# ESP32_LED_Matrix.net
KiCad netlist of a schematic drawn in Altium Designer
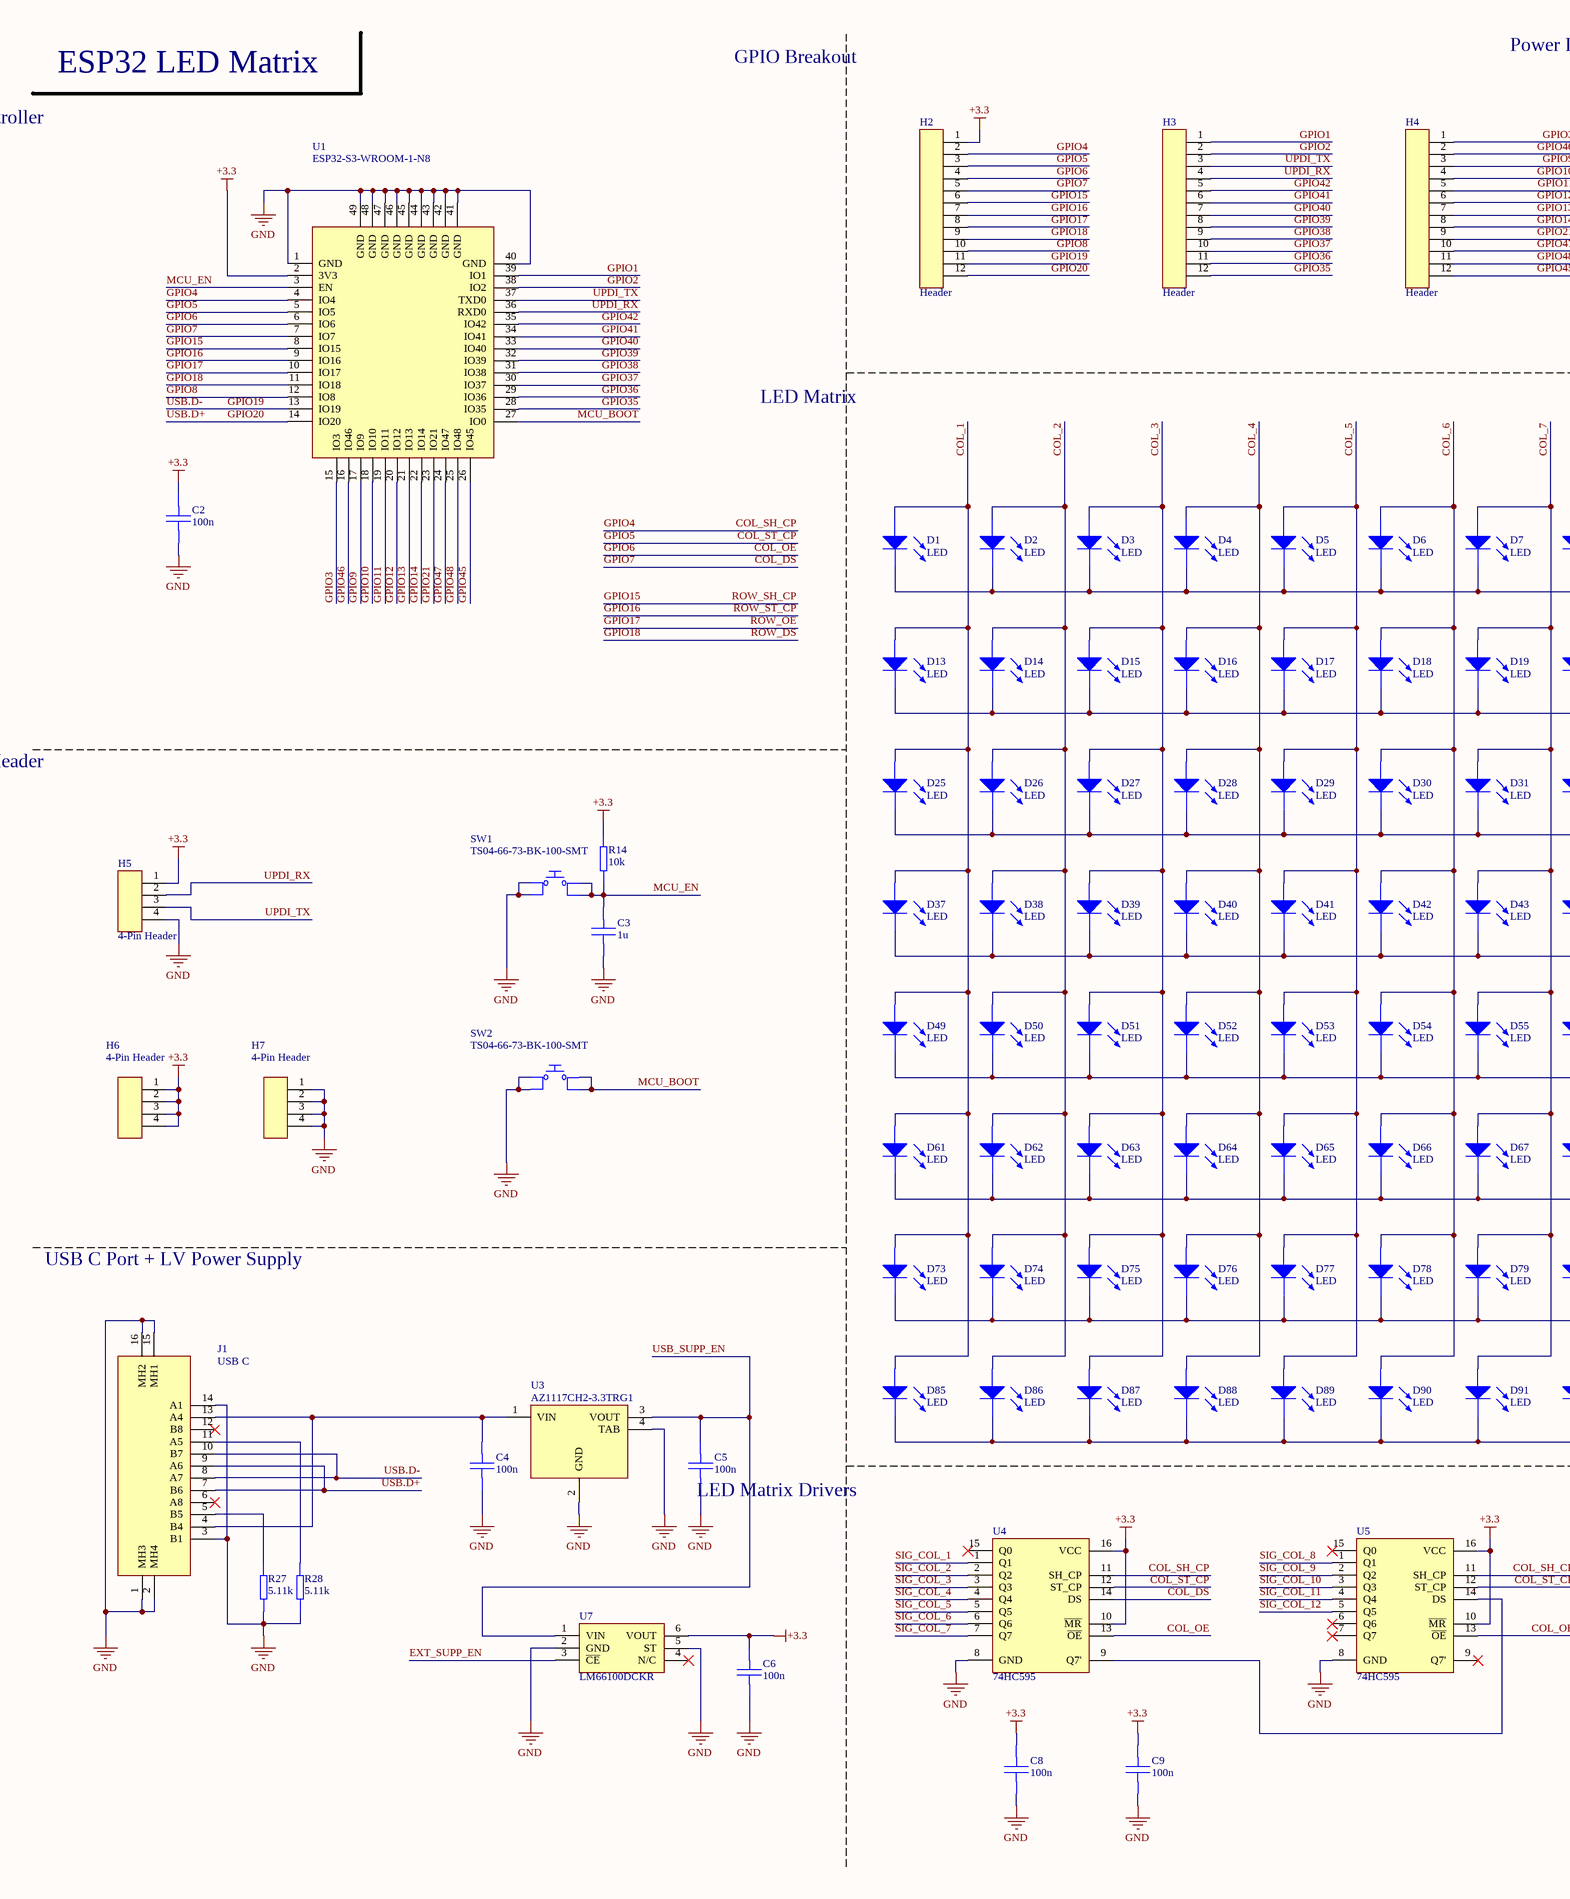
[diagram p0: ESP32_LED_Matrix.SchDoc, left]
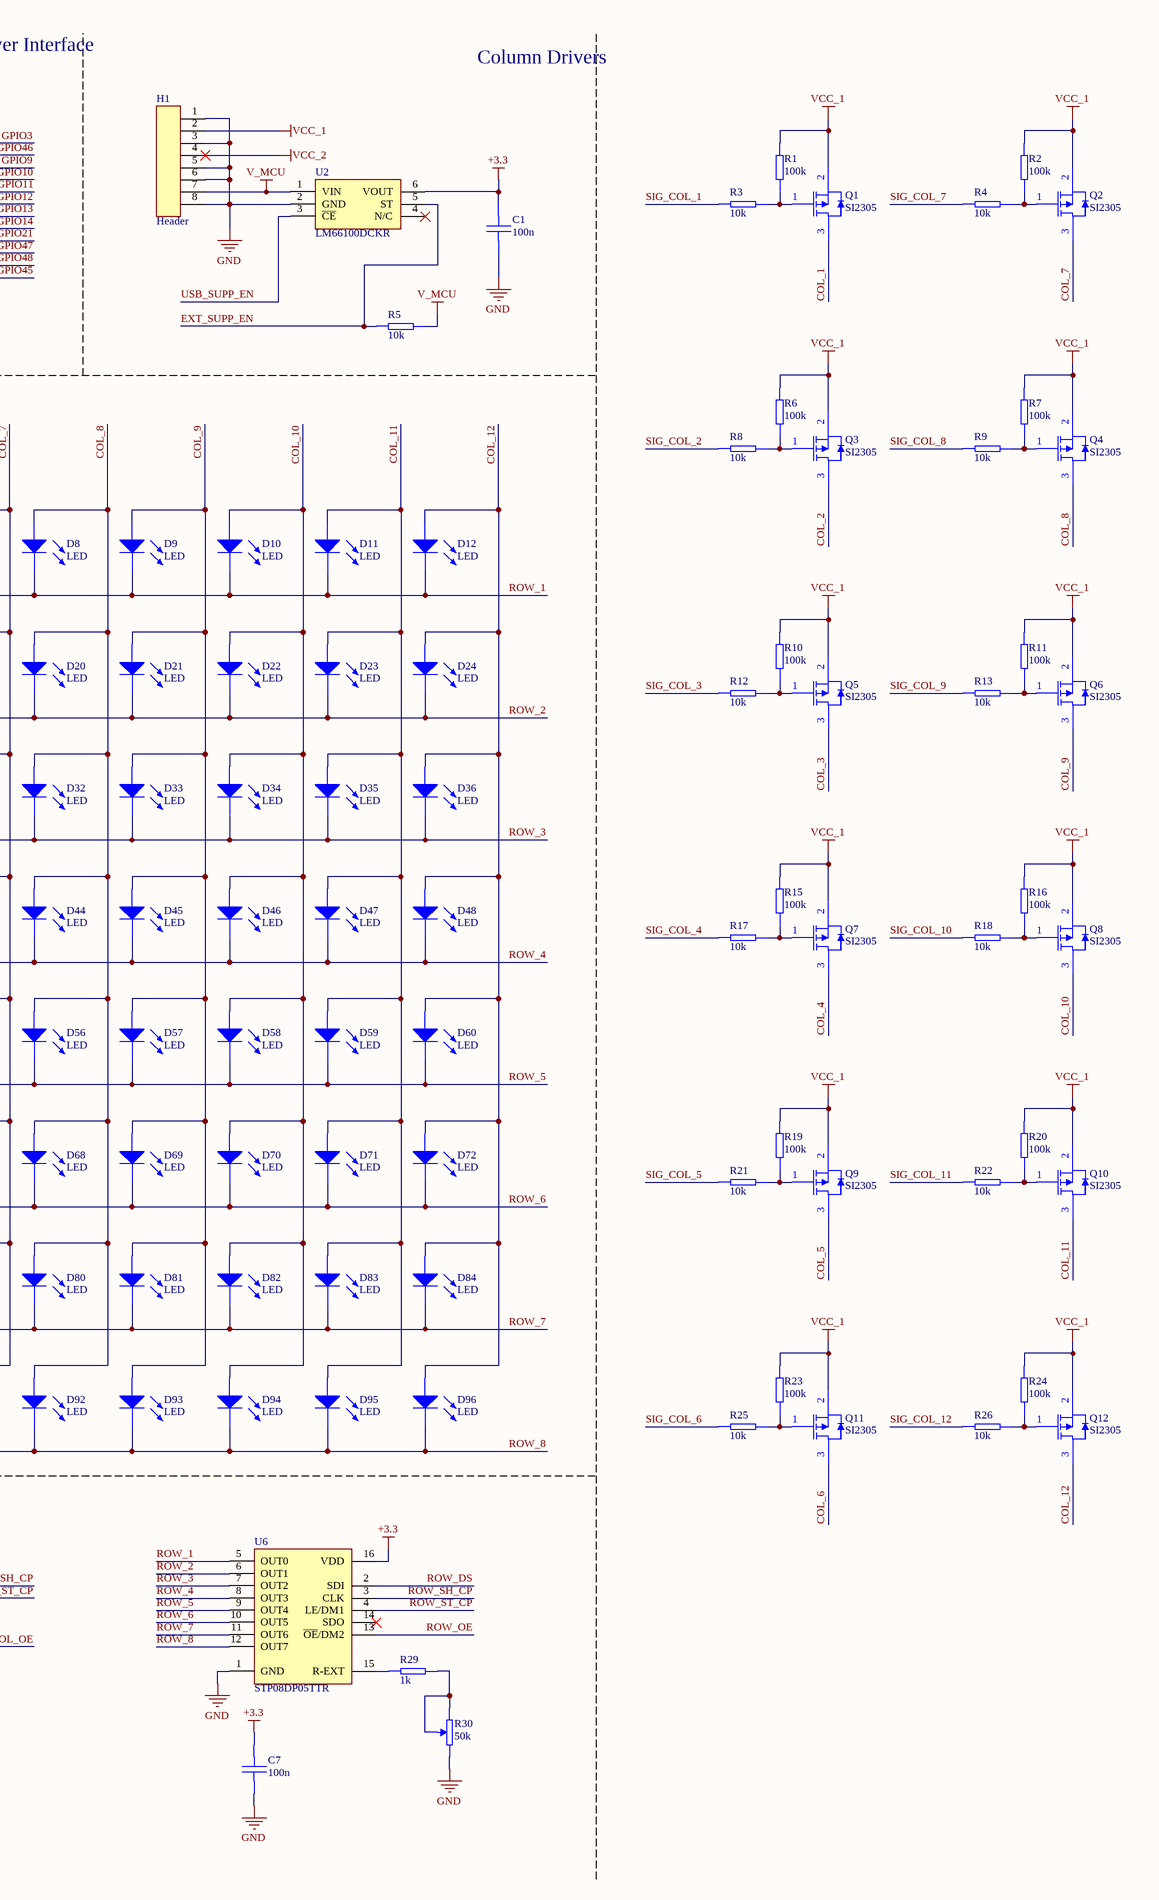
[diagram p1: ESP32_LED_Matrix.SchDoc, right]

(export (version "E")
  (design (tool "Eeschema 10.0.6"))
  (components
    (comp (ref "C1")
      (value "100n")
      (footprint "CAP0805")
      (description "Non Polarized Capacitor")
      (libsource (lib "HT2.2") (part "Capacitor - Non Polarized"))
    )
    (comp (ref "C2")
      (value "100n")
      (footprint "CAP0805")
      (description "Non Polarized Capacitor")
      (libsource (lib "HT2.2") (part "Capacitor - Non Polarized"))
    )
    (comp (ref "C3")
      (value "1u")
      (footprint "CAP0805")
      (description "Non Polarized Capacitor")
      (libsource (lib "HT2.2") (part "Capacitor - Non Polarized"))
    )
    (comp (ref "C4")
      (value "100n")
      (footprint "CAP0805")
      (description "Non Polarized Capacitor")
      (libsource (lib "TD") (part "Capacitor - Non Polarized"))
    )
    (comp (ref "C5")
      (value "100n")
      (footprint "CAP0805")
      (description "Non Polarized Capacitor")
      (libsource (lib "HT2.2") (part "Capacitor - Non Polarized"))
    )
    (comp (ref "C6")
      (value "100n")
      (footprint "CAP0805")
      (description "Non Polarized Capacitor")
      (libsource (lib "HT2.2") (part "Capacitor - Non Polarized"))
    )
    (comp (ref "C7")
      (value "100n")
      (footprint "CAP0805")
      (description "Non Polarized Capacitor")
      (libsource (lib "TD") (part "Capacitor - Non Polarized"))
    )
    (comp (ref "C8")
      (value "100n")
      (footprint "CAP0805")
      (description "Non Polarized Capacitor")
      (libsource (lib "TD") (part "Capacitor - Non Polarized"))
    )
    (comp (ref "C9")
      (value "100n")
      (footprint "CAP0805")
      (description "Non Polarized Capacitor")
      (libsource (lib "TD") (part "Capacitor - Non Polarized"))
    )
    (comp (ref "D1")
      (value "LED")
      (footprint "LEDM2012X80N")
      (description "General Purpose LED")
      (libsource (lib "TD") (part "LED"))
    )
    (comp (ref "D2")
      (value "LED")
      (footprint "LEDM2012X80N")
      (description "General Purpose LED")
      (libsource (lib "TD") (part "LED"))
    )
    (comp (ref "D3")
      (value "LED")
      (footprint "LEDM2012X80N")
      (description "General Purpose LED")
      (libsource (lib "TD") (part "LED"))
    )
    (comp (ref "D4")
      (value "LED")
      (footprint "LEDM2012X80N")
      (description "General Purpose LED")
      (libsource (lib "TD") (part "LED"))
    )
    (comp (ref "D5")
      (value "LED")
      (footprint "LEDM2012X80N")
      (description "General Purpose LED")
      (libsource (lib "TD") (part "LED"))
    )
    (comp (ref "D6")
      (value "LED")
      (footprint "LEDM2012X80N")
      (description "General Purpose LED")
      (libsource (lib "TD") (part "LED"))
    )
    (comp (ref "D7")
      (value "LED")
      (footprint "LEDM2012X80N")
      (description "General Purpose LED")
      (libsource (lib "TD") (part "LED"))
    )
    (comp (ref "D8")
      (value "LED")
      (footprint "LEDM2012X80N")
      (description "General Purpose LED")
      (libsource (lib "TD") (part "LED"))
    )
    (comp (ref "D9")
      (value "LED")
      (footprint "LEDM2012X80N")
      (description "General Purpose LED")
      (libsource (lib "TD") (part "LED"))
    )
    (comp (ref "D10")
      (value "LED")
      (footprint "LEDM2012X80N")
      (description "General Purpose LED")
      (libsource (lib "TD") (part "LED"))
    )
    (comp (ref "D11")
      (value "LED")
      (footprint "LEDM2012X80N")
      (description "General Purpose LED")
      (libsource (lib "TD") (part "LED"))
    )
    (comp (ref "D12")
      (value "LED")
      (footprint "LEDM2012X80N")
      (description "General Purpose LED")
      (libsource (lib "TD") (part "LED"))
    )
    (comp (ref "D13")
      (value "LED")
      (footprint "LEDM2012X80N")
      (description "General Purpose LED")
      (libsource (lib "TD") (part "LED"))
    )
    (comp (ref "D14")
      (value "LED")
      (footprint "LEDM2012X80N")
      (description "General Purpose LED")
      (libsource (lib "TD") (part "LED"))
    )
    (comp (ref "D15")
      (value "LED")
      (footprint "LEDM2012X80N")
      (description "General Purpose LED")
      (libsource (lib "TD") (part "LED"))
    )
    (comp (ref "D16")
      (value "LED")
      (footprint "LEDM2012X80N")
      (description "General Purpose LED")
      (libsource (lib "TD") (part "LED"))
    )
    (comp (ref "D17")
      (value "LED")
      (footprint "LEDM2012X80N")
      (description "General Purpose LED")
      (libsource (lib "TD") (part "LED"))
    )
    (comp (ref "D18")
      (value "LED")
      (footprint "LEDM2012X80N")
      (description "General Purpose LED")
      (libsource (lib "TD") (part "LED"))
    )
    (comp (ref "D19")
      (value "LED")
      (footprint "LEDM2012X80N")
      (description "General Purpose LED")
      (libsource (lib "TD") (part "LED"))
    )
    (comp (ref "D20")
      (value "LED")
      (footprint "LEDM2012X80N")
      (description "General Purpose LED")
      (libsource (lib "TD") (part "LED"))
    )
    (comp (ref "D21")
      (value "LED")
      (footprint "LEDM2012X80N")
      (description "General Purpose LED")
      (libsource (lib "TD") (part "LED"))
    )
    (comp (ref "D22")
      (value "LED")
      (footprint "LEDM2012X80N")
      (description "General Purpose LED")
      (libsource (lib "TD") (part "LED"))
    )
    (comp (ref "D23")
      (value "LED")
      (footprint "LEDM2012X80N")
      (description "General Purpose LED")
      (libsource (lib "TD") (part "LED"))
    )
    (comp (ref "D24")
      (value "LED")
      (footprint "LEDM2012X80N")
      (description "General Purpose LED")
      (libsource (lib "TD") (part "LED"))
    )
    (comp (ref "D25")
      (value "LED")
      (footprint "LEDM2012X80N")
      (description "General Purpose LED")
      (libsource (lib "TD") (part "LED"))
    )
    (comp (ref "D26")
      (value "LED")
      (footprint "LEDM2012X80N")
      (description "General Purpose LED")
      (libsource (lib "TD") (part "LED"))
    )
    (comp (ref "D27")
      (value "LED")
      (footprint "LEDM2012X80N")
      (description "General Purpose LED")
      (libsource (lib "TD") (part "LED"))
    )
    (comp (ref "D28")
      (value "LED")
      (footprint "LEDM2012X80N")
      (description "General Purpose LED")
      (libsource (lib "TD") (part "LED"))
    )
    (comp (ref "D29")
      (value "LED")
      (footprint "LEDM2012X80N")
      (description "General Purpose LED")
      (libsource (lib "TD") (part "LED"))
    )
    (comp (ref "D30")
      (value "LED")
      (footprint "LEDM2012X80N")
      (description "General Purpose LED")
      (libsource (lib "TD") (part "LED"))
    )
    (comp (ref "D31")
      (value "LED")
      (footprint "LEDM2012X80N")
      (description "General Purpose LED")
      (libsource (lib "TD") (part "LED"))
    )
    (comp (ref "D32")
      (value "LED")
      (footprint "LEDM2012X80N")
      (description "General Purpose LED")
      (libsource (lib "TD") (part "LED"))
    )
    (comp (ref "D33")
      (value "LED")
      (footprint "LEDM2012X80N")
      (description "General Purpose LED")
      (libsource (lib "TD") (part "LED"))
    )
    (comp (ref "D34")
      (value "LED")
      (footprint "LEDM2012X80N")
      (description "General Purpose LED")
      (libsource (lib "TD") (part "LED"))
    )
    (comp (ref "D35")
      (value "LED")
      (footprint "LEDM2012X80N")
      (description "General Purpose LED")
      (libsource (lib "TD") (part "LED"))
    )
    (comp (ref "D36")
      (value "LED")
      (footprint "LEDM2012X80N")
      (description "General Purpose LED")
      (libsource (lib "TD") (part "LED"))
    )
    (comp (ref "D37")
      (value "LED")
      (footprint "LEDM2012X80N")
      (description "General Purpose LED")
      (libsource (lib "TD") (part "LED"))
    )
    (comp (ref "D38")
      (value "LED")
      (footprint "LEDM2012X80N")
      (description "General Purpose LED")
      (libsource (lib "TD") (part "LED"))
    )
    (comp (ref "D39")
      (value "LED")
      (footprint "LEDM2012X80N")
      (description "General Purpose LED")
      (libsource (lib "TD") (part "LED"))
    )
    (comp (ref "D40")
      (value "LED")
      (footprint "LEDM2012X80N")
      (description "General Purpose LED")
      (libsource (lib "TD") (part "LED"))
    )
    (comp (ref "D41")
      (value "LED")
      (footprint "LEDM2012X80N")
      (description "General Purpose LED")
      (libsource (lib "TD") (part "LED"))
    )
    (comp (ref "D42")
      (value "LED")
      (footprint "LEDM2012X80N")
      (description "General Purpose LED")
      (libsource (lib "TD") (part "LED"))
    )
    (comp (ref "D43")
      (value "LED")
      (footprint "LEDM2012X80N")
      (description "General Purpose LED")
      (libsource (lib "TD") (part "LED"))
    )
    (comp (ref "D44")
      (value "LED")
      (footprint "LEDM2012X80N")
      (description "General Purpose LED")
      (libsource (lib "TD") (part "LED"))
    )
    (comp (ref "D45")
      (value "LED")
      (footprint "LEDM2012X80N")
      (description "General Purpose LED")
      (libsource (lib "TD") (part "LED"))
    )
    (comp (ref "D46")
      (value "LED")
      (footprint "LEDM2012X80N")
      (description "General Purpose LED")
      (libsource (lib "TD") (part "LED"))
    )
    (comp (ref "D47")
      (value "LED")
      (footprint "LEDM2012X80N")
      (description "General Purpose LED")
      (libsource (lib "TD") (part "LED"))
    )
    (comp (ref "D48")
      (value "LED")
      (footprint "LEDM2012X80N")
      (description "General Purpose LED")
      (libsource (lib "TD") (part "LED"))
    )
    (comp (ref "D49")
      (value "LED")
      (footprint "LEDM2012X80N")
      (description "General Purpose LED")
      (libsource (lib "TD") (part "LED"))
    )
    (comp (ref "D50")
      (value "LED")
      (footprint "LEDM2012X80N")
      (description "General Purpose LED")
      (libsource (lib "TD") (part "LED"))
    )
    (comp (ref "D51")
      (value "LED")
      (footprint "LEDM2012X80N")
      (description "General Purpose LED")
      (libsource (lib "TD") (part "LED"))
    )
    (comp (ref "D52")
      (value "LED")
      (footprint "LEDM2012X80N")
      (description "General Purpose LED")
      (libsource (lib "TD") (part "LED"))
    )
    (comp (ref "D53")
      (value "LED")
      (footprint "LEDM2012X80N")
      (description "General Purpose LED")
      (libsource (lib "TD") (part "LED"))
    )
    (comp (ref "D54")
      (value "LED")
      (footprint "LEDM2012X80N")
      (description "General Purpose LED")
      (libsource (lib "TD") (part "LED"))
    )
    (comp (ref "D55")
      (value "LED")
      (footprint "LEDM2012X80N")
      (description "General Purpose LED")
      (libsource (lib "TD") (part "LED"))
    )
    (comp (ref "D56")
      (value "LED")
      (footprint "LEDM2012X80N")
      (description "General Purpose LED")
      (libsource (lib "TD") (part "LED"))
    )
    (comp (ref "D57")
      (value "LED")
      (footprint "LEDM2012X80N")
      (description "General Purpose LED")
      (libsource (lib "TD") (part "LED"))
    )
    (comp (ref "D58")
      (value "LED")
      (footprint "LEDM2012X80N")
      (description "General Purpose LED")
      (libsource (lib "TD") (part "LED"))
    )
    (comp (ref "D59")
      (value "LED")
      (footprint "LEDM2012X80N")
      (description "General Purpose LED")
      (libsource (lib "TD") (part "LED"))
    )
    (comp (ref "D60")
      (value "LED")
      (footprint "LEDM2012X80N")
      (description "General Purpose LED")
      (libsource (lib "TD") (part "LED"))
    )
    (comp (ref "D61")
      (value "LED")
      (footprint "LEDM2012X80N")
      (description "General Purpose LED")
      (libsource (lib "TD") (part "LED"))
    )
    (comp (ref "D62")
      (value "LED")
      (footprint "LEDM2012X80N")
      (description "General Purpose LED")
      (libsource (lib "TD") (part "LED"))
    )
    (comp (ref "D63")
      (value "LED")
      (footprint "LEDM2012X80N")
      (description "General Purpose LED")
      (libsource (lib "TD") (part "LED"))
    )
    (comp (ref "D64")
      (value "LED")
      (footprint "LEDM2012X80N")
      (description "General Purpose LED")
      (libsource (lib "TD") (part "LED"))
    )
    (comp (ref "D65")
      (value "LED")
      (footprint "LEDM2012X80N")
      (description "General Purpose LED")
      (libsource (lib "TD") (part "LED"))
    )
    (comp (ref "D66")
      (value "LED")
      (footprint "LEDM2012X80N")
      (description "General Purpose LED")
      (libsource (lib "TD") (part "LED"))
    )
    (comp (ref "D67")
      (value "LED")
      (footprint "LEDM2012X80N")
      (description "General Purpose LED")
      (libsource (lib "TD") (part "LED"))
    )
    (comp (ref "D68")
      (value "LED")
      (footprint "LEDM2012X80N")
      (description "General Purpose LED")
      (libsource (lib "TD") (part "LED"))
    )
    (comp (ref "D69")
      (value "LED")
      (footprint "LEDM2012X80N")
      (description "General Purpose LED")
      (libsource (lib "TD") (part "LED"))
    )
    (comp (ref "D70")
      (value "LED")
      (footprint "LEDM2012X80N")
      (description "General Purpose LED")
      (libsource (lib "TD") (part "LED"))
    )
    (comp (ref "D71")
      (value "LED")
      (footprint "LEDM2012X80N")
      (description "General Purpose LED")
      (libsource (lib "TD") (part "LED"))
    )
    (comp (ref "D72")
      (value "LED")
      (footprint "LEDM2012X80N")
      (description "General Purpose LED")
      (libsource (lib "TD") (part "LED"))
    )
    (comp (ref "D73")
      (value "LED")
      (footprint "LEDM2012X80N")
      (description "General Purpose LED")
      (libsource (lib "TD") (part "LED"))
    )
    (comp (ref "D74")
      (value "LED")
      (footprint "LEDM2012X80N")
      (description "General Purpose LED")
      (libsource (lib "TD") (part "LED"))
    )
    (comp (ref "D75")
      (value "LED")
      (footprint "LEDM2012X80N")
      (description "General Purpose LED")
      (libsource (lib "TD") (part "LED"))
    )
    (comp (ref "D76")
      (value "LED")
      (footprint "LEDM2012X80N")
      (description "General Purpose LED")
      (libsource (lib "TD") (part "LED"))
    )
    (comp (ref "D77")
      (value "LED")
      (footprint "LEDM2012X80N")
      (description "General Purpose LED")
      (libsource (lib "TD") (part "LED"))
    )
    (comp (ref "D78")
      (value "LED")
      (footprint "LEDM2012X80N")
      (description "General Purpose LED")
      (libsource (lib "TD") (part "LED"))
    )
    (comp (ref "D79")
      (value "LED")
      (footprint "LEDM2012X80N")
      (description "General Purpose LED")
      (libsource (lib "TD") (part "LED"))
    )
    (comp (ref "D80")
      (value "LED")
      (footprint "LEDM2012X80N")
      (description "General Purpose LED")
      (libsource (lib "TD") (part "LED"))
    )
    (comp (ref "D81")
      (value "LED")
      (footprint "LEDM2012X80N")
      (description "General Purpose LED")
      (libsource (lib "TD") (part "LED"))
    )
    (comp (ref "D82")
      (value "LED")
      (footprint "LEDM2012X80N")
      (description "General Purpose LED")
      (libsource (lib "TD") (part "LED"))
    )
    (comp (ref "D83")
      (value "LED")
      (footprint "LEDM2012X80N")
      (description "General Purpose LED")
      (libsource (lib "TD") (part "LED"))
    )
    (comp (ref "D84")
      (value "LED")
      (footprint "LEDM2012X80N")
      (description "General Purpose LED")
      (libsource (lib "TD") (part "LED"))
    )
    (comp (ref "D85")
      (value "LED")
      (footprint "LEDM2012X80N")
      (description "General Purpose LED")
      (libsource (lib "TD") (part "LED"))
    )
    (comp (ref "D86")
      (value "LED")
      (footprint "LEDM2012X80N")
      (description "General Purpose LED")
      (libsource (lib "TD") (part "LED"))
    )
    (comp (ref "D87")
      (value "LED")
      (footprint "LEDM2012X80N")
      (description "General Purpose LED")
      (libsource (lib "TD") (part "LED"))
    )
    (comp (ref "D88")
      (value "LED")
      (footprint "LEDM2012X80N")
      (description "General Purpose LED")
      (libsource (lib "TD") (part "LED"))
    )
    (comp (ref "D89")
      (value "LED")
      (footprint "LEDM2012X80N")
      (description "General Purpose LED")
      (libsource (lib "TD") (part "LED"))
    )
    (comp (ref "D90")
      (value "LED")
      (footprint "LEDM2012X80N")
      (description "General Purpose LED")
      (libsource (lib "TD") (part "LED"))
    )
    (comp (ref "D91")
      (value "LED")
      (footprint "LEDM2012X80N")
      (description "General Purpose LED")
      (libsource (lib "TD") (part "LED"))
    )
    (comp (ref "D92")
      (value "LED")
      (footprint "LEDM2012X80N")
      (description "General Purpose LED")
      (libsource (lib "TD") (part "LED"))
    )
    (comp (ref "D93")
      (value "LED")
      (footprint "LEDM2012X80N")
      (description "General Purpose LED")
      (libsource (lib "TD") (part "LED"))
    )
    (comp (ref "D94")
      (value "LED")
      (footprint "LEDM2012X80N")
      (description "General Purpose LED")
      (libsource (lib "TD") (part "LED"))
    )
    (comp (ref "D95")
      (value "LED")
      (footprint "LEDM2012X80N")
      (description "General Purpose LED")
      (libsource (lib "TD") (part "LED"))
    )
    (comp (ref "D96")
      (value "LED")
      (footprint "LEDM2012X80N")
      (description "General Purpose LED")
      (libsource (lib "TD") (part "LED"))
    )
    (comp (ref "H1")
      (value "Header")
      (footprint "Header_1X8")
      (description "8-Pin Header")
      (libsource (lib "TD") (part "8-Pin Header"))
    )
    (comp (ref "H2")
      (value "Header")
      (footprint "Header_1X12")
      (description "12-Pin Header")
      (libsource (lib "TD") (part "12-Pin Header"))
    )
    (comp (ref "H3")
      (value "Header")
      (footprint "Header_1X12")
      (description "12-Pin Header")
      (libsource (lib "TD") (part "12-Pin Header"))
    )
    (comp (ref "H4")
      (value "Header")
      (footprint "Header_1X12")
      (description "12-Pin Header")
      (libsource (lib "TD") (part "12-Pin Header"))
    )
    (comp (ref "H5")
      (value "4-Pin Header")
      (footprint "Header_1X4")
      (libsource (lib "TD") (part "4-Pin Header"))
    )
    (comp (ref "H6")
      (value "4-Pin Header")
      (footprint "Header_1X4")
      (libsource (lib "TD") (part "4-Pin Header"))
    )
    (comp (ref "H7")
      (value "4-Pin Header")
      (footprint "Header_1X4")
      (libsource (lib "TD") (part "4-Pin Header"))
    )
    (comp (ref "J1")
      (value "USB C")
      (footprint "USB TYPE C 12 PIN")
      (libsource (lib "TD") (part "USB Type C Connector 12 Pin"))
    )
    (comp (ref "Q1")
      (value "SI2305")
      (footprint "SOT23")
      (description "General Purpose P-Channel MOSFET")
      (libsource (lib "TD") (part "SI2305"))
    )
    (comp (ref "Q2")
      (value "SI2305")
      (footprint "SOT23")
      (description "General Purpose P-Channel MOSFET")
      (libsource (lib "TD") (part "SI2305"))
    )
    (comp (ref "Q3")
      (value "SI2305")
      (footprint "SOT23")
      (description "General Purpose P-Channel MOSFET")
      (libsource (lib "TD") (part "SI2305"))
    )
    (comp (ref "Q4")
      (value "SI2305")
      (footprint "SOT23")
      (description "General Purpose P-Channel MOSFET")
      (libsource (lib "TD") (part "SI2305"))
    )
    (comp (ref "Q5")
      (value "SI2305")
      (footprint "SOT23")
      (description "General Purpose P-Channel MOSFET")
      (libsource (lib "TD") (part "SI2305"))
    )
    (comp (ref "Q6")
      (value "SI2305")
      (footprint "SOT23")
      (description "General Purpose P-Channel MOSFET")
      (libsource (lib "TD") (part "SI2305"))
    )
    (comp (ref "Q7")
      (value "SI2305")
      (footprint "SOT23")
      (description "General Purpose P-Channel MOSFET")
      (libsource (lib "TD") (part "SI2305"))
    )
    (comp (ref "Q8")
      (value "SI2305")
      (footprint "SOT23")
      (description "General Purpose P-Channel MOSFET")
      (libsource (lib "TD") (part "SI2305"))
    )
    (comp (ref "Q9")
      (value "SI2305")
      (footprint "SOT23")
      (description "General Purpose P-Channel MOSFET")
      (libsource (lib "TD") (part "SI2305"))
    )
    (comp (ref "Q10")
      (value "SI2305")
      (footprint "SOT23")
      (description "General Purpose P-Channel MOSFET")
      (libsource (lib "TD") (part "SI2305"))
    )
    (comp (ref "Q11")
      (value "SI2305")
      (footprint "SOT23")
      (description "General Purpose P-Channel MOSFET")
      (libsource (lib "TD") (part "SI2305"))
    )
    (comp (ref "Q12")
      (value "SI2305")
      (footprint "SOT23")
      (description "General Purpose P-Channel MOSFET")
      (libsource (lib "TD") (part "SI2305"))
    )
    (comp (ref "R1")
      (value "100k")
      (footprint "RESC0805")
      (description "Resistor")
      (libsource (lib "TD") (part "Resistor"))
    )
    (comp (ref "R2")
      (value "100k")
      (footprint "RESC0805")
      (description "Resistor")
      (libsource (lib "TD") (part "Resistor"))
    )
    (comp (ref "R3")
      (value "10k")
      (footprint "RESC0805")
      (description "Resistor")
      (libsource (lib "TD") (part "Resistor"))
    )
    (comp (ref "R4")
      (value "10k")
      (footprint "RESC0805")
      (description "Resistor")
      (libsource (lib "TD") (part "Resistor"))
    )
    (comp (ref "R5")
      (value "10k")
      (footprint "RESC0805")
      (description "Resistor")
      (libsource (lib "TD") (part "Resistor"))
    )
    (comp (ref "R6")
      (value "100k")
      (footprint "RESC0805")
      (description "Resistor")
      (libsource (lib "TD") (part "Resistor"))
    )
    (comp (ref "R7")
      (value "100k")
      (footprint "RESC0805")
      (description "Resistor")
      (libsource (lib "TD") (part "Resistor"))
    )
    (comp (ref "R8")
      (value "10k")
      (footprint "RESC0805")
      (description "Resistor")
      (libsource (lib "TD") (part "Resistor"))
    )
    (comp (ref "R9")
      (value "10k")
      (footprint "RESC0805")
      (description "Resistor")
      (libsource (lib "TD") (part "Resistor"))
    )
    (comp (ref "R10")
      (value "100k")
      (footprint "RESC0805")
      (description "Resistor")
      (libsource (lib "TD") (part "Resistor"))
    )
    (comp (ref "R11")
      (value "100k")
      (footprint "RESC0805")
      (description "Resistor")
      (libsource (lib "TD") (part "Resistor"))
    )
    (comp (ref "R12")
      (value "10k")
      (footprint "RESC0805")
      (description "Resistor")
      (libsource (lib "TD") (part "Resistor"))
    )
    (comp (ref "R13")
      (value "10k")
      (footprint "RESC0805")
      (description "Resistor")
      (libsource (lib "TD") (part "Resistor"))
    )
    (comp (ref "R14")
      (value "10k")
      (footprint "RESC0805")
      (description "Resistor")
      (libsource (lib "TD") (part "Resistor"))
    )
    (comp (ref "R15")
      (value "100k")
      (footprint "RESC0805")
      (description "Resistor")
      (libsource (lib "TD") (part "Resistor"))
    )
    (comp (ref "R16")
      (value "100k")
      (footprint "RESC0805")
      (description "Resistor")
      (libsource (lib "TD") (part "Resistor"))
    )
    (comp (ref "R17")
      (value "10k")
      (footprint "RESC0805")
      (description "Resistor")
      (libsource (lib "TD") (part "Resistor"))
    )
    (comp (ref "R18")
      (value "10k")
      (footprint "RESC0805")
      (description "Resistor")
      (libsource (lib "TD") (part "Resistor"))
    )
    (comp (ref "R19")
      (value "100k")
      (footprint "RESC0805")
      (description "Resistor")
      (libsource (lib "TD") (part "Resistor"))
    )
    (comp (ref "R20")
      (value "100k")
      (footprint "RESC0805")
      (description "Resistor")
      (libsource (lib "TD") (part "Resistor"))
    )
    (comp (ref "R21")
      (value "10k")
      (footprint "RESC0805")
      (description "Resistor")
      (libsource (lib "TD") (part "Resistor"))
    )
    (comp (ref "R22")
      (value "10k")
      (footprint "RESC0805")
      (description "Resistor")
      (libsource (lib "TD") (part "Resistor"))
    )
    (comp (ref "R23")
      (value "100k")
      (footprint "RESC0805")
      (description "Resistor")
      (libsource (lib "TD") (part "Resistor"))
    )
    (comp (ref "R24")
      (value "100k")
      (footprint "RESC0805")
      (description "Resistor")
      (libsource (lib "TD") (part "Resistor"))
    )
    (comp (ref "R25")
      (value "10k")
      (footprint "RESC0805")
      (description "Resistor")
      (libsource (lib "TD") (part "Resistor"))
    )
    (comp (ref "R26")
      (value "10k")
      (footprint "RESC0805")
      (description "Resistor")
      (libsource (lib "TD") (part "Resistor"))
    )
    (comp (ref "R27")
      (value "5.11k")
      (footprint "RESC0805")
      (description "Resistor")
      (libsource (lib "HT2.2") (part "Resistor"))
    )
    (comp (ref "R28")
      (value "5.11k")
      (footprint "RESC0805")
      (description "Resistor")
      (libsource (lib "HT2.2") (part "Resistor"))
    )
    (comp (ref "R29")
      (value "1k")
      (footprint "RESC0805")
      (description "Resistor")
      (libsource (lib "TD") (part "Resistor"))
    )
    (comp (ref "R30")
      (value "50k")
      (footprint "3339P1103LF")
      (description "Potentionmeter")
      (libsource (lib "TD") (part "Potentiometer"))
    )
    (comp (ref "SW1")
      (value "TS04-66-73-BK-100-SMT")
      (footprint "Tactile Button 6.0mm x 6.0mm")
      (description "Switch")
      (fields (field (name "MOUSER PART NUMBER") "179-TS046673BK100SMT"))
      (libsource (lib "TD") (part "TS04-66-73-BK-100-SMT"))
    )
    (comp (ref "SW2")
      (value "TS04-66-73-BK-100-SMT")
      (footprint "Tactile Button 6.0mm x 6.0mm")
      (description "Switch")
      (fields (field (name "MOUSER PART NUMBER") "179-TS046673BK100SMT"))
      (libsource (lib "TD") (part "TS04-66-73-BK-100-SMT"))
    )
    (comp (ref "U1")
      (value "ESP32-S3-WROOM-1-N8")
      (footprint "ESP32-S3-WROOM-1-N8")
      (description "ESP32 Microcontroller with Bluetooth and Wifi")
      (libsource (lib "HT2.3") (part "ESP32-S3-WROOM-1-N8"))
    )
    (comp (ref "U2")
      (value "LM66100DCKR")
      (footprint "SC70-6")
      (description "5.5-V, 1.5-A 79-mΩ, Low IQ Ideal Diode With Input Polarity Protection")
      (fields (field (name "MOUSER PART NUMBER") "595-LM66100DCKR"))
      (libsource (lib "TD") (part "LM66100DCKR"))
    )
    (comp (ref "U3")
      (value "AZ1117CH2-3.3TRG1")
      (footprint "SOT223")
      (description "3.3V Linear Voltage Regulator")
      (libsource (lib "TD") (part "AZ1117CH2-3.3TRG1_1"))
    )
    (comp (ref "U4")
      (value "74HC595")
      (footprint "TSSOP16")
      (description "Shift Register")
      (libsource (lib "TD") (part "74HC595"))
    )
    (comp (ref "U5")
      (value "74HC595")
      (footprint "TSSOP16")
      (description "Shift Register")
      (libsource (lib "TD") (part "74HC595"))
    )
    (comp (ref "U6")
      (value "STP08DP05TTR")
      (footprint "TSSOP16")
      (description "LED Driver")
      (fields (field (name "MOUSER PART NUMBER") "511-STP08DP05TTR"))
      (libsource (lib "TD") (part "STP08DP05TTR"))
    )
    (comp (ref "U7")
      (value "LM66100DCKR")
      (footprint "SC70-6")
      (description "5.5-V, 1.5-A 79-mΩ, Low IQ Ideal Diode With Input Polarity Protection")
      (fields (field (name "MOUSER PART NUMBER") "595-LM66100DCKR"))
      (libsource (lib "TD") (part "LM66100DCKR"))
    )
  )
  (nets
    (net (code "1") (name "+3.3") (class "Default")
      (node (ref "C1") (pin "1") (pintype "passive"))
      (node (ref "C2") (pin "1") (pintype "passive"))
      (node (ref "C6") (pin "1") (pintype "passive"))
      (node (ref "C7") (pin "1") (pintype "passive"))
      (node (ref "C8") (pin "1") (pintype "passive"))
      (node (ref "C9") (pin "1") (pintype "passive"))
      (node (ref "H2") (pin "1") (pintype "passive"))
      (node (ref "H5") (pin "1") (pintype "passive"))
      (node (ref "H6") (pin "1") (pintype "passive"))
      (node (ref "H6") (pin "2") (pintype "passive"))
      (node (ref "H6") (pin "3") (pintype "passive"))
      (node (ref "H6") (pin "4") (pintype "passive"))
      (node (ref "R14") (pin "1") (pintype "passive"))
      (node (ref "U1") (pin "2") (pinfunction "3V3_2") (pintype "passive"))
      (node (ref "U2") (pin "6") (pinfunction "VOUT_6") (pintype "passive"))
      (node (ref "U4") (pin "10") (pinfunction "~{MR}_10") (pintype "passive"))
      (node (ref "U4") (pin "16") (pinfunction "VCC_16") (pintype "passive"))
      (node (ref "U5") (pin "10") (pinfunction "~{MR}_10") (pintype "passive"))
      (node (ref "U5") (pin "16") (pinfunction "VCC_16") (pintype "passive"))
      (node (ref "U6") (pin "16") (pinfunction "VDD_16") (pintype "passive"))
      (node (ref "U7") (pin "6") (pinfunction "VOUT_6") (pintype "passive"))
    )
    (net (code "2") (name "/COL_1") (class "Default")
      (node (ref "D1") (pin "2") (pinfunction "A_2") (pintype "passive"))
      (node (ref "D13") (pin "2") (pinfunction "A_2") (pintype "passive"))
      (node (ref "D25") (pin "2") (pinfunction "A_2") (pintype "passive"))
      (node (ref "D37") (pin "2") (pinfunction "A_2") (pintype "passive"))
      (node (ref "D49") (pin "2") (pinfunction "A_2") (pintype "passive"))
      (node (ref "D61") (pin "2") (pinfunction "A_2") (pintype "passive"))
      (node (ref "D73") (pin "2") (pinfunction "A_2") (pintype "passive"))
      (node (ref "D85") (pin "2") (pinfunction "A_2") (pintype "passive"))
      (node (ref "Q1") (pin "3") (pinfunction "D_3") (pintype "passive"))
    )
    (net (code "3") (name "/COL_2") (class "Default")
      (node (ref "D14") (pin "2") (pinfunction "A_2") (pintype "passive"))
      (node (ref "D2") (pin "2") (pinfunction "A_2") (pintype "passive"))
      (node (ref "D26") (pin "2") (pinfunction "A_2") (pintype "passive"))
      (node (ref "D38") (pin "2") (pinfunction "A_2") (pintype "passive"))
      (node (ref "D50") (pin "2") (pinfunction "A_2") (pintype "passive"))
      (node (ref "D62") (pin "2") (pinfunction "A_2") (pintype "passive"))
      (node (ref "D74") (pin "2") (pinfunction "A_2") (pintype "passive"))
      (node (ref "D86") (pin "2") (pinfunction "A_2") (pintype "passive"))
      (node (ref "Q3") (pin "3") (pinfunction "D_3") (pintype "passive"))
    )
    (net (code "4") (name "/COL_3") (class "Default")
      (node (ref "D15") (pin "2") (pinfunction "A_2") (pintype "passive"))
      (node (ref "D27") (pin "2") (pinfunction "A_2") (pintype "passive"))
      (node (ref "D3") (pin "2") (pinfunction "A_2") (pintype "passive"))
      (node (ref "D39") (pin "2") (pinfunction "A_2") (pintype "passive"))
      (node (ref "D51") (pin "2") (pinfunction "A_2") (pintype "passive"))
      (node (ref "D63") (pin "2") (pinfunction "A_2") (pintype "passive"))
      (node (ref "D75") (pin "2") (pinfunction "A_2") (pintype "passive"))
      (node (ref "D87") (pin "2") (pinfunction "A_2") (pintype "passive"))
      (node (ref "Q5") (pin "3") (pinfunction "D_3") (pintype "passive"))
    )
    (net (code "5") (name "/COL_4") (class "Default")
      (node (ref "D16") (pin "2") (pinfunction "A_2") (pintype "passive"))
      (node (ref "D28") (pin "2") (pinfunction "A_2") (pintype "passive"))
      (node (ref "D4") (pin "2") (pinfunction "A_2") (pintype "passive"))
      (node (ref "D40") (pin "2") (pinfunction "A_2") (pintype "passive"))
      (node (ref "D52") (pin "2") (pinfunction "A_2") (pintype "passive"))
      (node (ref "D64") (pin "2") (pinfunction "A_2") (pintype "passive"))
      (node (ref "D76") (pin "2") (pinfunction "A_2") (pintype "passive"))
      (node (ref "D88") (pin "2") (pinfunction "A_2") (pintype "passive"))
      (node (ref "Q7") (pin "3") (pinfunction "D_3") (pintype "passive"))
    )
    (net (code "6") (name "/COL_5") (class "Default")
      (node (ref "D17") (pin "2") (pinfunction "A_2") (pintype "passive"))
      (node (ref "D29") (pin "2") (pinfunction "A_2") (pintype "passive"))
      (node (ref "D41") (pin "2") (pinfunction "A_2") (pintype "passive"))
      (node (ref "D5") (pin "2") (pinfunction "A_2") (pintype "passive"))
      (node (ref "D53") (pin "2") (pinfunction "A_2") (pintype "passive"))
      (node (ref "D65") (pin "2") (pinfunction "A_2") (pintype "passive"))
      (node (ref "D77") (pin "2") (pinfunction "A_2") (pintype "passive"))
      (node (ref "D89") (pin "2") (pinfunction "A_2") (pintype "passive"))
      (node (ref "Q9") (pin "3") (pinfunction "D_3") (pintype "passive"))
    )
    (net (code "7") (name "/COL_6") (class "Default")
      (node (ref "D18") (pin "2") (pinfunction "A_2") (pintype "passive"))
      (node (ref "D30") (pin "2") (pinfunction "A_2") (pintype "passive"))
      (node (ref "D42") (pin "2") (pinfunction "A_2") (pintype "passive"))
      (node (ref "D54") (pin "2") (pinfunction "A_2") (pintype "passive"))
      (node (ref "D6") (pin "2") (pinfunction "A_2") (pintype "passive"))
      (node (ref "D66") (pin "2") (pinfunction "A_2") (pintype "passive"))
      (node (ref "D78") (pin "2") (pinfunction "A_2") (pintype "passive"))
      (node (ref "D90") (pin "2") (pinfunction "A_2") (pintype "passive"))
      (node (ref "Q11") (pin "3") (pinfunction "D_3") (pintype "passive"))
    )
    (net (code "8") (name "/COL_7") (class "Default")
      (node (ref "D19") (pin "2") (pinfunction "A_2") (pintype "passive"))
      (node (ref "D31") (pin "2") (pinfunction "A_2") (pintype "passive"))
      (node (ref "D43") (pin "2") (pinfunction "A_2") (pintype "passive"))
      (node (ref "D55") (pin "2") (pinfunction "A_2") (pintype "passive"))
      (node (ref "D67") (pin "2") (pinfunction "A_2") (pintype "passive"))
      (node (ref "D7") (pin "2") (pinfunction "A_2") (pintype "passive"))
      (node (ref "D79") (pin "2") (pinfunction "A_2") (pintype "passive"))
      (node (ref "D91") (pin "2") (pinfunction "A_2") (pintype "passive"))
      (node (ref "Q2") (pin "3") (pinfunction "D_3") (pintype "passive"))
    )
    (net (code "9") (name "/COL_8") (class "Default")
      (node (ref "D20") (pin "2") (pinfunction "A_2") (pintype "passive"))
      (node (ref "D32") (pin "2") (pinfunction "A_2") (pintype "passive"))
      (node (ref "D44") (pin "2") (pinfunction "A_2") (pintype "passive"))
      (node (ref "D56") (pin "2") (pinfunction "A_2") (pintype "passive"))
      (node (ref "D68") (pin "2") (pinfunction "A_2") (pintype "passive"))
      (node (ref "D8") (pin "2") (pinfunction "A_2") (pintype "passive"))
      (node (ref "D80") (pin "2") (pinfunction "A_2") (pintype "passive"))
      (node (ref "D92") (pin "2") (pinfunction "A_2") (pintype "passive"))
      (node (ref "Q4") (pin "3") (pinfunction "D_3") (pintype "passive"))
    )
    (net (code "10") (name "/COL_9") (class "Default")
      (node (ref "D21") (pin "2") (pinfunction "A_2") (pintype "passive"))
      (node (ref "D33") (pin "2") (pinfunction "A_2") (pintype "passive"))
      (node (ref "D45") (pin "2") (pinfunction "A_2") (pintype "passive"))
      (node (ref "D57") (pin "2") (pinfunction "A_2") (pintype "passive"))
      (node (ref "D69") (pin "2") (pinfunction "A_2") (pintype "passive"))
      (node (ref "D81") (pin "2") (pinfunction "A_2") (pintype "passive"))
      (node (ref "D9") (pin "2") (pinfunction "A_2") (pintype "passive"))
      (node (ref "D93") (pin "2") (pinfunction "A_2") (pintype "passive"))
      (node (ref "Q6") (pin "3") (pinfunction "D_3") (pintype "passive"))
    )
    (net (code "11") (name "/COL_10") (class "Default")
      (node (ref "D10") (pin "2") (pinfunction "A_2") (pintype "passive"))
      (node (ref "D22") (pin "2") (pinfunction "A_2") (pintype "passive"))
      (node (ref "D34") (pin "2") (pinfunction "A_2") (pintype "passive"))
      (node (ref "D46") (pin "2") (pinfunction "A_2") (pintype "passive"))
      (node (ref "D58") (pin "2") (pinfunction "A_2") (pintype "passive"))
      (node (ref "D70") (pin "2") (pinfunction "A_2") (pintype "passive"))
      (node (ref "D82") (pin "2") (pinfunction "A_2") (pintype "passive"))
      (node (ref "D94") (pin "2") (pinfunction "A_2") (pintype "passive"))
      (node (ref "Q8") (pin "3") (pinfunction "D_3") (pintype "passive"))
    )
    (net (code "12") (name "/COL_11") (class "Default")
      (node (ref "D11") (pin "2") (pinfunction "A_2") (pintype "passive"))
      (node (ref "D23") (pin "2") (pinfunction "A_2") (pintype "passive"))
      (node (ref "D35") (pin "2") (pinfunction "A_2") (pintype "passive"))
      (node (ref "D47") (pin "2") (pinfunction "A_2") (pintype "passive"))
      (node (ref "D59") (pin "2") (pinfunction "A_2") (pintype "passive"))
      (node (ref "D71") (pin "2") (pinfunction "A_2") (pintype "passive"))
      (node (ref "D83") (pin "2") (pinfunction "A_2") (pintype "passive"))
      (node (ref "D95") (pin "2") (pinfunction "A_2") (pintype "passive"))
      (node (ref "Q10") (pin "3") (pinfunction "D_3") (pintype "passive"))
    )
    (net (code "13") (name "/COL_12") (class "Default")
      (node (ref "D12") (pin "2") (pinfunction "A_2") (pintype "passive"))
      (node (ref "D24") (pin "2") (pinfunction "A_2") (pintype "passive"))
      (node (ref "D36") (pin "2") (pinfunction "A_2") (pintype "passive"))
      (node (ref "D48") (pin "2") (pinfunction "A_2") (pintype "passive"))
      (node (ref "D60") (pin "2") (pinfunction "A_2") (pintype "passive"))
      (node (ref "D72") (pin "2") (pinfunction "A_2") (pintype "passive"))
      (node (ref "D84") (pin "2") (pinfunction "A_2") (pintype "passive"))
      (node (ref "D96") (pin "2") (pinfunction "A_2") (pintype "passive"))
      (node (ref "Q12") (pin "3") (pinfunction "D_3") (pintype "passive"))
    )
    (net (code "14") (name "/COL_DS") (class "Default")
      (node (ref "H2") (pin "5") (pintype "passive"))
      (node (ref "U1") (pin "7") (pinfunction "IO7_7") (pintype "passive"))
      (node (ref "U4") (pin "14") (pinfunction "DS_14") (pintype "passive"))
    )
    (net (code "15") (name "/COL_OE") (class "Default")
      (node (ref "H2") (pin "4") (pintype "passive"))
      (node (ref "U1") (pin "6") (pinfunction "IO6_6") (pintype "passive"))
      (node (ref "U4") (pin "13") (pinfunction "~{OE}_13") (pintype "passive"))
      (node (ref "U5") (pin "13") (pinfunction "~{OE}_13") (pintype "passive"))
    )
    (net (code "16") (name "/COL_SH_CP") (class "Default")
      (node (ref "H2") (pin "2") (pintype "passive"))
      (node (ref "U1") (pin "4") (pinfunction "IO4_4") (pintype "passive"))
      (node (ref "U4") (pin "11") (pinfunction "SH_CP_11") (pintype "passive"))
      (node (ref "U5") (pin "11") (pinfunction "SH_CP_11") (pintype "passive"))
    )
    (net (code "17") (name "/COL_ST_CP") (class "Default")
      (node (ref "H2") (pin "3") (pintype "passive"))
      (node (ref "U1") (pin "5") (pinfunction "IO5_5") (pintype "passive"))
      (node (ref "U4") (pin "12") (pinfunction "ST_CP_12") (pintype "passive"))
      (node (ref "U5") (pin "12") (pinfunction "ST_CP_12") (pintype "passive"))
    )
    (net (code "18") (name "/EXT_SUPP_EN") (class "Default")
      (node (ref "R5") (pin "1") (pintype "passive"))
      (node (ref "U2") (pin "5") (pinfunction "ST_5") (pintype "passive"))
      (node (ref "U7") (pin "3") (pinfunction "~{CE}_3") (pintype "passive"))
    )
    (net (code "19") (name "/GPIO1") (class "Default")
      (node (ref "H3") (pin "1") (pintype "passive"))
      (node (ref "U1") (pin "39") (pinfunction "IO1_39") (pintype "passive"))
    )
    (net (code "20") (name "/GPIO2") (class "Default")
      (node (ref "H3") (pin "2") (pintype "passive"))
      (node (ref "U1") (pin "38") (pinfunction "IO2_38") (pintype "passive"))
    )
    (net (code "21") (name "/GPIO3") (class "Default")
      (node (ref "H4") (pin "1") (pintype "passive"))
      (node (ref "U1") (pin "15") (pinfunction "IO3_15") (pintype "passive"))
    )
    (net (code "22") (name "/GPIO8") (class "Default")
      (node (ref "H2") (pin "10") (pintype "passive"))
      (node (ref "U1") (pin "12") (pinfunction "IO8_12") (pintype "passive"))
    )
    (net (code "23") (name "/GPIO9") (class "Default")
      (node (ref "H4") (pin "3") (pintype "passive"))
      (node (ref "U1") (pin "17") (pinfunction "IO9_17") (pintype "passive"))
    )
    (net (code "24") (name "/GPIO10") (class "Default")
      (node (ref "H4") (pin "4") (pintype "passive"))
      (node (ref "U1") (pin "18") (pinfunction "IO10_18") (pintype "passive"))
    )
    (net (code "25") (name "/GPIO11") (class "Default")
      (node (ref "H4") (pin "5") (pintype "passive"))
      (node (ref "U1") (pin "19") (pinfunction "IO11_19") (pintype "passive"))
    )
    (net (code "26") (name "/GPIO12") (class "Default")
      (node (ref "H4") (pin "6") (pintype "passive"))
      (node (ref "U1") (pin "20") (pinfunction "IO12_20") (pintype "passive"))
    )
    (net (code "27") (name "/GPIO13") (class "Default")
      (node (ref "H4") (pin "7") (pintype "passive"))
      (node (ref "U1") (pin "21") (pinfunction "IO13_21") (pintype "passive"))
    )
    (net (code "28") (name "/GPIO14") (class "Default")
      (node (ref "H4") (pin "8") (pintype "passive"))
      (node (ref "U1") (pin "22") (pinfunction "IO14_22") (pintype "passive"))
    )
    (net (code "29") (name "/GPIO15") (class "Default")
      (node (ref "H2") (pin "6") (pintype "passive"))
      (node (ref "U1") (pin "8") (pinfunction "IO15_8") (pintype "passive"))
      (node (ref "U6") (pin "3") (pinfunction "CLK_3") (pintype "passive"))
    )
    (net (code "30") (name "/GPIO16") (class "Default")
      (node (ref "H2") (pin "7") (pintype "passive"))
      (node (ref "U1") (pin "9") (pinfunction "IO16_9") (pintype "passive"))
      (node (ref "U6") (pin "4") (pinfunction "LE/DM1_4") (pintype "passive"))
    )
    (net (code "31") (name "/GPIO17") (class "Default")
      (node (ref "H2") (pin "8") (pintype "passive"))
      (node (ref "U1") (pin "10") (pinfunction "IO17_10") (pintype "passive"))
      (node (ref "U6") (pin "13") (pinfunction "~{OE}/DM2_13") (pintype "passive"))
    )
    (net (code "32") (name "/GPIO18") (class "Default")
      (node (ref "H2") (pin "9") (pintype "passive"))
      (node (ref "U1") (pin "11") (pinfunction "IO18_11") (pintype "passive"))
      (node (ref "U6") (pin "2") (pinfunction "SDI_2") (pintype "passive"))
    )
    (net (code "33") (name "/GPIO19") (class "Default")
      (node (ref "H2") (pin "11") (pintype "passive"))
      (node (ref "J1") (pin "10") (pinfunction "B7_10") (pintype "passive"))
      (node (ref "J1") (pin "8") (pinfunction "A7_8") (pintype "passive"))
      (node (ref "U1") (pin "13") (pinfunction "IO19_13") (pintype "passive"))
    )
    (net (code "34") (name "/GPIO20") (class "Default")
      (node (ref "H2") (pin "12") (pintype "passive"))
      (node (ref "J1") (pin "7") (pinfunction "B6_7") (pintype "passive"))
      (node (ref "J1") (pin "9") (pinfunction "A6_9") (pintype "passive"))
      (node (ref "U1") (pin "14") (pinfunction "IO20_14") (pintype "passive"))
    )
    (net (code "35") (name "/GPIO21") (class "Default")
      (node (ref "H4") (pin "9") (pintype "passive"))
      (node (ref "U1") (pin "23") (pinfunction "IO21_23") (pintype "passive"))
    )
    (net (code "36") (name "/GPIO35") (class "Default")
      (node (ref "H3") (pin "12") (pintype "passive"))
      (node (ref "U1") (pin "28") (pinfunction "IO35_28") (pintype "passive"))
    )
    (net (code "37") (name "/GPIO36") (class "Default")
      (node (ref "H3") (pin "11") (pintype "passive"))
      (node (ref "U1") (pin "29") (pinfunction "IO36_29") (pintype "passive"))
    )
    (net (code "38") (name "/GPIO37") (class "Default")
      (node (ref "H3") (pin "10") (pintype "passive"))
      (node (ref "U1") (pin "30") (pinfunction "IO37_30") (pintype "passive"))
    )
    (net (code "39") (name "/GPIO38") (class "Default")
      (node (ref "H3") (pin "9") (pintype "passive"))
      (node (ref "U1") (pin "31") (pinfunction "IO38_31") (pintype "passive"))
    )
    (net (code "40") (name "/GPIO39") (class "Default")
      (node (ref "H3") (pin "8") (pintype "passive"))
      (node (ref "U1") (pin "32") (pinfunction "IO39_32") (pintype "passive"))
    )
    (net (code "41") (name "/GPIO40") (class "Default")
      (node (ref "H3") (pin "7") (pintype "passive"))
      (node (ref "U1") (pin "33") (pinfunction "IO40_33") (pintype "passive"))
    )
    (net (code "42") (name "/GPIO41") (class "Default")
      (node (ref "H3") (pin "6") (pintype "passive"))
      (node (ref "U1") (pin "34") (pinfunction "IO41_34") (pintype "passive"))
    )
    (net (code "43") (name "/GPIO42") (class "Default")
      (node (ref "H3") (pin "5") (pintype "passive"))
      (node (ref "U1") (pin "35") (pinfunction "IO42_35") (pintype "passive"))
    )
    (net (code "44") (name "/GPIO45") (class "Default")
      (node (ref "H4") (pin "12") (pintype "passive"))
      (node (ref "U1") (pin "26") (pinfunction "IO45_26") (pintype "passive"))
    )
    (net (code "45") (name "/GPIO46") (class "Default")
      (node (ref "H4") (pin "2") (pintype "passive"))
      (node (ref "U1") (pin "16") (pinfunction "IO46_16") (pintype "passive"))
    )
    (net (code "46") (name "/GPIO47") (class "Default")
      (node (ref "H4") (pin "10") (pintype "passive"))
      (node (ref "U1") (pin "24") (pinfunction "IO47_24") (pintype "passive"))
    )
    (net (code "47") (name "/GPIO48") (class "Default")
      (node (ref "H4") (pin "11") (pintype "passive"))
      (node (ref "U1") (pin "25") (pinfunction "IO48_25") (pintype "passive"))
    )
    (net (code "48") (name "/MCU_BOOT") (class "Default")
      (node (ref "SW2") (pin "3") (pintype "passive"))
      (node (ref "SW2") (pin "4") (pintype "passive"))
      (node (ref "U1") (pin "27") (pinfunction "IO0_27") (pintype "passive"))
    )
    (net (code "49") (name "/MCU_EN") (class "Default")
      (node (ref "C3") (pin "1") (pintype "passive"))
      (node (ref "R14") (pin "2") (pintype "passive"))
      (node (ref "SW1") (pin "3") (pintype "passive"))
      (node (ref "SW1") (pin "4") (pintype "passive"))
      (node (ref "U1") (pin "3") (pinfunction "EN_3") (pintype "passive"))
    )
    (net (code "50") (name "/ROW_1") (class "Default")
      (node (ref "D1") (pin "1") (pinfunction "K_1") (pintype "passive"))
      (node (ref "D10") (pin "1") (pinfunction "K_1") (pintype "passive"))
      (node (ref "D11") (pin "1") (pinfunction "K_1") (pintype "passive"))
      (node (ref "D12") (pin "1") (pinfunction "K_1") (pintype "passive"))
      (node (ref "D2") (pin "1") (pinfunction "K_1") (pintype "passive"))
      (node (ref "D3") (pin "1") (pinfunction "K_1") (pintype "passive"))
      (node (ref "D4") (pin "1") (pinfunction "K_1") (pintype "passive"))
      (node (ref "D5") (pin "1") (pinfunction "K_1") (pintype "passive"))
      (node (ref "D6") (pin "1") (pinfunction "K_1") (pintype "passive"))
      (node (ref "D7") (pin "1") (pinfunction "K_1") (pintype "passive"))
      (node (ref "D8") (pin "1") (pinfunction "K_1") (pintype "passive"))
      (node (ref "D9") (pin "1") (pinfunction "K_1") (pintype "passive"))
      (node (ref "U6") (pin "5") (pinfunction "OUT0_5") (pintype "passive"))
    )
    (net (code "51") (name "/ROW_2") (class "Default")
      (node (ref "D13") (pin "1") (pinfunction "K_1") (pintype "passive"))
      (node (ref "D14") (pin "1") (pinfunction "K_1") (pintype "passive"))
      (node (ref "D15") (pin "1") (pinfunction "K_1") (pintype "passive"))
      (node (ref "D16") (pin "1") (pinfunction "K_1") (pintype "passive"))
      (node (ref "D17") (pin "1") (pinfunction "K_1") (pintype "passive"))
      (node (ref "D18") (pin "1") (pinfunction "K_1") (pintype "passive"))
      (node (ref "D19") (pin "1") (pinfunction "K_1") (pintype "passive"))
      (node (ref "D20") (pin "1") (pinfunction "K_1") (pintype "passive"))
      (node (ref "D21") (pin "1") (pinfunction "K_1") (pintype "passive"))
      (node (ref "D22") (pin "1") (pinfunction "K_1") (pintype "passive"))
      (node (ref "D23") (pin "1") (pinfunction "K_1") (pintype "passive"))
      (node (ref "D24") (pin "1") (pinfunction "K_1") (pintype "passive"))
      (node (ref "U6") (pin "6") (pinfunction "OUT1_6") (pintype "passive"))
    )
    (net (code "52") (name "/ROW_3") (class "Default")
      (node (ref "D25") (pin "1") (pinfunction "K_1") (pintype "passive"))
      (node (ref "D26") (pin "1") (pinfunction "K_1") (pintype "passive"))
      (node (ref "D27") (pin "1") (pinfunction "K_1") (pintype "passive"))
      (node (ref "D28") (pin "1") (pinfunction "K_1") (pintype "passive"))
      (node (ref "D29") (pin "1") (pinfunction "K_1") (pintype "passive"))
      (node (ref "D30") (pin "1") (pinfunction "K_1") (pintype "passive"))
      (node (ref "D31") (pin "1") (pinfunction "K_1") (pintype "passive"))
      (node (ref "D32") (pin "1") (pinfunction "K_1") (pintype "passive"))
      (node (ref "D33") (pin "1") (pinfunction "K_1") (pintype "passive"))
      (node (ref "D34") (pin "1") (pinfunction "K_1") (pintype "passive"))
      (node (ref "D35") (pin "1") (pinfunction "K_1") (pintype "passive"))
      (node (ref "D36") (pin "1") (pinfunction "K_1") (pintype "passive"))
      (node (ref "U6") (pin "7") (pinfunction "OUT2_7") (pintype "passive"))
    )
    (net (code "53") (name "/ROW_4") (class "Default")
      (node (ref "D37") (pin "1") (pinfunction "K_1") (pintype "passive"))
      (node (ref "D38") (pin "1") (pinfunction "K_1") (pintype "passive"))
      (node (ref "D39") (pin "1") (pinfunction "K_1") (pintype "passive"))
      (node (ref "D40") (pin "1") (pinfunction "K_1") (pintype "passive"))
      (node (ref "D41") (pin "1") (pinfunction "K_1") (pintype "passive"))
      (node (ref "D42") (pin "1") (pinfunction "K_1") (pintype "passive"))
      (node (ref "D43") (pin "1") (pinfunction "K_1") (pintype "passive"))
      (node (ref "D44") (pin "1") (pinfunction "K_1") (pintype "passive"))
      (node (ref "D45") (pin "1") (pinfunction "K_1") (pintype "passive"))
      (node (ref "D46") (pin "1") (pinfunction "K_1") (pintype "passive"))
      (node (ref "D47") (pin "1") (pinfunction "K_1") (pintype "passive"))
      (node (ref "D48") (pin "1") (pinfunction "K_1") (pintype "passive"))
      (node (ref "U6") (pin "8") (pinfunction "OUT3_8") (pintype "passive"))
    )
    (net (code "54") (name "/ROW_5") (class "Default")
      (node (ref "D49") (pin "1") (pinfunction "K_1") (pintype "passive"))
      (node (ref "D50") (pin "1") (pinfunction "K_1") (pintype "passive"))
      (node (ref "D51") (pin "1") (pinfunction "K_1") (pintype "passive"))
      (node (ref "D52") (pin "1") (pinfunction "K_1") (pintype "passive"))
      (node (ref "D53") (pin "1") (pinfunction "K_1") (pintype "passive"))
      (node (ref "D54") (pin "1") (pinfunction "K_1") (pintype "passive"))
      (node (ref "D55") (pin "1") (pinfunction "K_1") (pintype "passive"))
      (node (ref "D56") (pin "1") (pinfunction "K_1") (pintype "passive"))
      (node (ref "D57") (pin "1") (pinfunction "K_1") (pintype "passive"))
      (node (ref "D58") (pin "1") (pinfunction "K_1") (pintype "passive"))
      (node (ref "D59") (pin "1") (pinfunction "K_1") (pintype "passive"))
      (node (ref "D60") (pin "1") (pinfunction "K_1") (pintype "passive"))
      (node (ref "U6") (pin "9") (pinfunction "OUT4_9") (pintype "passive"))
    )
    (net (code "55") (name "/ROW_6") (class "Default")
      (node (ref "D61") (pin "1") (pinfunction "K_1") (pintype "passive"))
      (node (ref "D62") (pin "1") (pinfunction "K_1") (pintype "passive"))
      (node (ref "D63") (pin "1") (pinfunction "K_1") (pintype "passive"))
      (node (ref "D64") (pin "1") (pinfunction "K_1") (pintype "passive"))
      (node (ref "D65") (pin "1") (pinfunction "K_1") (pintype "passive"))
      (node (ref "D66") (pin "1") (pinfunction "K_1") (pintype "passive"))
      (node (ref "D67") (pin "1") (pinfunction "K_1") (pintype "passive"))
      (node (ref "D68") (pin "1") (pinfunction "K_1") (pintype "passive"))
      (node (ref "D69") (pin "1") (pinfunction "K_1") (pintype "passive"))
      (node (ref "D70") (pin "1") (pinfunction "K_1") (pintype "passive"))
      (node (ref "D71") (pin "1") (pinfunction "K_1") (pintype "passive"))
      (node (ref "D72") (pin "1") (pinfunction "K_1") (pintype "passive"))
      (node (ref "U6") (pin "10") (pinfunction "OUT5_10") (pintype "passive"))
    )
    (net (code "56") (name "/ROW_7") (class "Default")
      (node (ref "D73") (pin "1") (pinfunction "K_1") (pintype "passive"))
      (node (ref "D74") (pin "1") (pinfunction "K_1") (pintype "passive"))
      (node (ref "D75") (pin "1") (pinfunction "K_1") (pintype "passive"))
      (node (ref "D76") (pin "1") (pinfunction "K_1") (pintype "passive"))
      (node (ref "D77") (pin "1") (pinfunction "K_1") (pintype "passive"))
      (node (ref "D78") (pin "1") (pinfunction "K_1") (pintype "passive"))
      (node (ref "D79") (pin "1") (pinfunction "K_1") (pintype "passive"))
      (node (ref "D80") (pin "1") (pinfunction "K_1") (pintype "passive"))
      (node (ref "D81") (pin "1") (pinfunction "K_1") (pintype "passive"))
      (node (ref "D82") (pin "1") (pinfunction "K_1") (pintype "passive"))
      (node (ref "D83") (pin "1") (pinfunction "K_1") (pintype "passive"))
      (node (ref "D84") (pin "1") (pinfunction "K_1") (pintype "passive"))
      (node (ref "U6") (pin "11") (pinfunction "OUT6_11") (pintype "passive"))
    )
    (net (code "57") (name "/ROW_8") (class "Default")
      (node (ref "D85") (pin "1") (pinfunction "K_1") (pintype "passive"))
      (node (ref "D86") (pin "1") (pinfunction "K_1") (pintype "passive"))
      (node (ref "D87") (pin "1") (pinfunction "K_1") (pintype "passive"))
      (node (ref "D88") (pin "1") (pinfunction "K_1") (pintype "passive"))
      (node (ref "D89") (pin "1") (pinfunction "K_1") (pintype "passive"))
      (node (ref "D90") (pin "1") (pinfunction "K_1") (pintype "passive"))
      (node (ref "D91") (pin "1") (pinfunction "K_1") (pintype "passive"))
      (node (ref "D92") (pin "1") (pinfunction "K_1") (pintype "passive"))
      (node (ref "D93") (pin "1") (pinfunction "K_1") (pintype "passive"))
      (node (ref "D94") (pin "1") (pinfunction "K_1") (pintype "passive"))
      (node (ref "D95") (pin "1") (pinfunction "K_1") (pintype "passive"))
      (node (ref "D96") (pin "1") (pinfunction "K_1") (pintype "passive"))
      (node (ref "U6") (pin "12") (pinfunction "OUT7_12") (pintype "passive"))
    )
    (net (code "58") (name "/SIG_COL_1") (class "Default")
      (node (ref "R3") (pin "1") (pintype "passive"))
      (node (ref "U4") (pin "1") (pinfunction "Q1_1") (pintype "passive"))
    )
    (net (code "59") (name "/SIG_COL_2") (class "Default")
      (node (ref "R8") (pin "1") (pintype "passive"))
      (node (ref "U4") (pin "2") (pinfunction "Q2_2") (pintype "passive"))
    )
    (net (code "60") (name "/SIG_COL_3") (class "Default")
      (node (ref "R12") (pin "1") (pintype "passive"))
      (node (ref "U4") (pin "3") (pinfunction "Q3_3") (pintype "passive"))
    )
    (net (code "61") (name "/SIG_COL_4") (class "Default")
      (node (ref "R17") (pin "1") (pintype "passive"))
      (node (ref "U4") (pin "4") (pinfunction "Q4_4") (pintype "passive"))
    )
    (net (code "62") (name "/SIG_COL_5") (class "Default")
      (node (ref "R21") (pin "1") (pintype "passive"))
      (node (ref "U4") (pin "5") (pinfunction "Q5_5") (pintype "passive"))
    )
    (net (code "63") (name "/SIG_COL_6") (class "Default")
      (node (ref "R25") (pin "1") (pintype "passive"))
      (node (ref "U4") (pin "6") (pinfunction "Q6_6") (pintype "passive"))
    )
    (net (code "64") (name "/SIG_COL_7") (class "Default")
      (node (ref "R4") (pin "1") (pintype "passive"))
      (node (ref "U4") (pin "7") (pinfunction "Q7_7") (pintype "passive"))
    )
    (net (code "65") (name "/SIG_COL_8") (class "Default")
      (node (ref "R9") (pin "1") (pintype "passive"))
      (node (ref "U5") (pin "1") (pinfunction "Q1_1") (pintype "passive"))
    )
    (net (code "66") (name "/SIG_COL_9") (class "Default")
      (node (ref "R13") (pin "1") (pintype "passive"))
      (node (ref "U5") (pin "2") (pinfunction "Q2_2") (pintype "passive"))
    )
    (net (code "67") (name "/SIG_COL_10") (class "Default")
      (node (ref "R18") (pin "1") (pintype "passive"))
      (node (ref "U5") (pin "3") (pinfunction "Q3_3") (pintype "passive"))
    )
    (net (code "68") (name "/SIG_COL_11") (class "Default")
      (node (ref "R22") (pin "1") (pintype "passive"))
      (node (ref "U5") (pin "4") (pinfunction "Q4_4") (pintype "passive"))
    )
    (net (code "69") (name "/SIG_COL_12") (class "Default")
      (node (ref "R26") (pin "1") (pintype "passive"))
      (node (ref "U5") (pin "5") (pinfunction "Q5_5") (pintype "passive"))
    )
    (net (code "70") (name "/UPDI_RX") (class "Default")
      (node (ref "H3") (pin "4") (pintype "passive"))
      (node (ref "H5") (pin "2") (pintype "passive"))
      (node (ref "U1") (pin "36") (pinfunction "RXD0_36") (pintype "passive"))
    )
    (net (code "71") (name "/UPDI_TX") (class "Default")
      (node (ref "H3") (pin "3") (pintype "passive"))
      (node (ref "H5") (pin "3") (pintype "passive"))
      (node (ref "U1") (pin "37") (pinfunction "TXD0_37") (pintype "passive"))
    )
    (net (code "72") (name "/USB_SUPP_EN") (class "Default")
      (node (ref "C5") (pin "1") (pintype "passive"))
      (node (ref "U2") (pin "3") (pinfunction "~{CE}_3") (pintype "passive"))
      (node (ref "U3") (pin "3") (pinfunction "VOUT_3") (pintype "passive"))
      (node (ref "U7") (pin "1") (pinfunction "VIN_1") (pintype "passive"))
    )
    (net (code "73") (name "GND") (class "Default")
      (node (ref "C1") (pin "2") (pintype "passive"))
      (node (ref "C2") (pin "2") (pintype "passive"))
      (node (ref "C3") (pin "2") (pintype "passive"))
      (node (ref "C4") (pin "2") (pintype "passive"))
      (node (ref "C5") (pin "2") (pintype "passive"))
      (node (ref "C6") (pin "2") (pintype "passive"))
      (node (ref "C7") (pin "2") (pintype "passive"))
      (node (ref "C8") (pin "2") (pintype "passive"))
      (node (ref "C9") (pin "2") (pintype "passive"))
      (node (ref "H1") (pin "1") (pintype "passive"))
      (node (ref "H1") (pin "3") (pintype "passive"))
      (node (ref "H1") (pin "5") (pintype "passive"))
      (node (ref "H1") (pin "6") (pintype "passive"))
      (node (ref "H1") (pin "8") (pintype "passive"))
      (node (ref "H5") (pin "4") (pintype "passive"))
      (node (ref "H7") (pin "1") (pintype "passive"))
      (node (ref "H7") (pin "2") (pintype "passive"))
      (node (ref "H7") (pin "3") (pintype "passive"))
      (node (ref "H7") (pin "4") (pintype "passive"))
      (node (ref "J1") (pin "1") (pinfunction "MH3_1") (pintype "passive"))
      (node (ref "J1") (pin "14") (pinfunction "A1_14") (pintype "passive"))
      (node (ref "J1") (pin "15") (pinfunction "MH1_15") (pintype "passive"))
      (node (ref "J1") (pin "16") (pinfunction "MH2_16") (pintype "passive"))
      (node (ref "J1") (pin "2") (pinfunction "MH4_2") (pintype "passive"))
      (node (ref "J1") (pin "3") (pinfunction "B1_3") (pintype "passive"))
      (node (ref "R27") (pin "1") (pintype "passive"))
      (node (ref "R28") (pin "1") (pintype "passive"))
      (node (ref "R30") (pin "3") (pintype "passive"))
      (node (ref "SW1") (pin "1") (pintype "passive"))
      (node (ref "SW1") (pin "2") (pintype "passive"))
      (node (ref "SW2") (pin "1") (pintype "passive"))
      (node (ref "SW2") (pin "2") (pintype "passive"))
      (node (ref "U1") (pin "1") (pinfunction "GND_1") (pintype "passive"))
      (node (ref "U1") (pin "40") (pinfunction "GND_40") (pintype "passive"))
      (node (ref "U1") (pin "41") (pinfunction "GND_41") (pintype "passive"))
      (node (ref "U1") (pin "42") (pinfunction "GND_42") (pintype "passive"))
      (node (ref "U1") (pin "43") (pinfunction "GND_43") (pintype "passive"))
      (node (ref "U1") (pin "44") (pinfunction "GND_44") (pintype "passive"))
      (node (ref "U1") (pin "45") (pinfunction "GND_45") (pintype "passive"))
      (node (ref "U1") (pin "46") (pinfunction "GND_46") (pintype "passive"))
      (node (ref "U1") (pin "47") (pinfunction "GND_47") (pintype "passive"))
      (node (ref "U1") (pin "48") (pinfunction "GND_48") (pintype "passive"))
      (node (ref "U1") (pin "49") (pinfunction "GND_49") (pintype "passive"))
      (node (ref "U2") (pin "2") (pinfunction "GND_2") (pintype "passive"))
      (node (ref "U3") (pin "2") (pinfunction "GND_2") (pintype "passive"))
      (node (ref "U3") (pin "4") (pinfunction "TAB_4") (pintype "passive"))
      (node (ref "U4") (pin "8") (pinfunction "GND_8") (pintype "passive"))
      (node (ref "U5") (pin "8") (pinfunction "GND_8") (pintype "passive"))
      (node (ref "U6") (pin "1") (pinfunction "GND_1") (pintype "passive"))
      (node (ref "U7") (pin "2") (pinfunction "GND_2") (pintype "passive"))
      (node (ref "U7") (pin "5") (pinfunction "ST_5") (pintype "passive"))
    )
    (net (code "74") (name "Net-(J1-A4)") (class "Default")
      (node (ref "C4") (pin "1") (pintype "passive"))
      (node (ref "J1") (pin "13") (pinfunction "A4_13") (pintype "passive"))
      (node (ref "J1") (pin "4") (pinfunction "B4_4") (pintype "passive"))
      (node (ref "U3") (pin "1") (pinfunction "VIN_1") (pintype "passive"))
    )
    (net (code "75") (name "Net-(J1-A5)") (class "Default")
      (node (ref "J1") (pin "11") (pinfunction "A5_11") (pintype "passive"))
      (node (ref "R28") (pin "2") (pintype "passive"))
    )
    (net (code "76") (name "Net-(J1-B5)") (class "Default")
      (node (ref "J1") (pin "5") (pinfunction "B5_5") (pintype "passive"))
      (node (ref "R27") (pin "2") (pintype "passive"))
    )
    (net (code "77") (name "Net-(Q1-G)") (class "Default")
      (node (ref "Q1") (pin "1") (pinfunction "G_1") (pintype "passive"))
      (node (ref "R1") (pin "2") (pintype "passive"))
      (node (ref "R3") (pin "2") (pintype "passive"))
    )
    (net (code "78") (name "Net-(Q2-G)") (class "Default")
      (node (ref "Q2") (pin "1") (pinfunction "G_1") (pintype "passive"))
      (node (ref "R2") (pin "2") (pintype "passive"))
      (node (ref "R4") (pin "2") (pintype "passive"))
    )
    (net (code "79") (name "Net-(Q3-G)") (class "Default")
      (node (ref "Q3") (pin "1") (pinfunction "G_1") (pintype "passive"))
      (node (ref "R6") (pin "2") (pintype "passive"))
      (node (ref "R8") (pin "2") (pintype "passive"))
    )
    (net (code "80") (name "Net-(Q4-G)") (class "Default")
      (node (ref "Q4") (pin "1") (pinfunction "G_1") (pintype "passive"))
      (node (ref "R7") (pin "2") (pintype "passive"))
      (node (ref "R9") (pin "2") (pintype "passive"))
    )
    (net (code "81") (name "Net-(Q5-G)") (class "Default")
      (node (ref "Q5") (pin "1") (pinfunction "G_1") (pintype "passive"))
      (node (ref "R10") (pin "2") (pintype "passive"))
      (node (ref "R12") (pin "2") (pintype "passive"))
    )
    (net (code "82") (name "Net-(Q6-G)") (class "Default")
      (node (ref "Q6") (pin "1") (pinfunction "G_1") (pintype "passive"))
      (node (ref "R11") (pin "2") (pintype "passive"))
      (node (ref "R13") (pin "2") (pintype "passive"))
    )
    (net (code "83") (name "Net-(Q7-G)") (class "Default")
      (node (ref "Q7") (pin "1") (pinfunction "G_1") (pintype "passive"))
      (node (ref "R15") (pin "2") (pintype "passive"))
      (node (ref "R17") (pin "2") (pintype "passive"))
    )
    (net (code "84") (name "Net-(Q8-G)") (class "Default")
      (node (ref "Q8") (pin "1") (pinfunction "G_1") (pintype "passive"))
      (node (ref "R16") (pin "2") (pintype "passive"))
      (node (ref "R18") (pin "2") (pintype "passive"))
    )
    (net (code "85") (name "Net-(Q9-G)") (class "Default")
      (node (ref "Q9") (pin "1") (pinfunction "G_1") (pintype "passive"))
      (node (ref "R19") (pin "2") (pintype "passive"))
      (node (ref "R21") (pin "2") (pintype "passive"))
    )
    (net (code "86") (name "Net-(Q10-G)") (class "Default")
      (node (ref "Q10") (pin "1") (pinfunction "G_1") (pintype "passive"))
      (node (ref "R20") (pin "2") (pintype "passive"))
      (node (ref "R22") (pin "2") (pintype "passive"))
    )
    (net (code "87") (name "Net-(Q11-G)") (class "Default")
      (node (ref "Q11") (pin "1") (pinfunction "G_1") (pintype "passive"))
      (node (ref "R23") (pin "2") (pintype "passive"))
      (node (ref "R25") (pin "2") (pintype "passive"))
    )
    (net (code "88") (name "Net-(Q12-G)") (class "Default")
      (node (ref "Q12") (pin "1") (pinfunction "G_1") (pintype "passive"))
      (node (ref "R24") (pin "2") (pintype "passive"))
      (node (ref "R26") (pin "2") (pintype "passive"))
    )
    (net (code "89") (name "Net-(R29-Pad2)") (class "Default")
      (node (ref "R29") (pin "2") (pintype "passive"))
      (node (ref "R30") (pin "1") (pintype "passive"))
      (node (ref "R30") (pin "2") (pintype "passive"))
    )
    (net (code "90") (name "Net-(U4-Q7')") (class "Default")
      (node (ref "U4") (pin "9") (pinfunction "Q7'_9") (pintype "passive"))
      (node (ref "U5") (pin "14") (pinfunction "DS_14") (pintype "passive"))
    )
    (net (code "91") (name "Net-(U6-R-EXT)") (class "Default")
      (node (ref "R29") (pin "1") (pintype "passive"))
      (node (ref "U6") (pin "15") (pinfunction "R-EXT_15") (pintype "passive"))
    )
    (net (code "92") (name "VCC_1") (class "Default")
      (node (ref "H1") (pin "2") (pintype "passive"))
      (node (ref "Q1") (pin "2") (pinfunction "S_2") (pintype "passive"))
      (node (ref "Q10") (pin "2") (pinfunction "S_2") (pintype "passive"))
      (node (ref "Q11") (pin "2") (pinfunction "S_2") (pintype "passive"))
      (node (ref "Q12") (pin "2") (pinfunction "S_2") (pintype "passive"))
      (node (ref "Q2") (pin "2") (pinfunction "S_2") (pintype "passive"))
      (node (ref "Q3") (pin "2") (pinfunction "S_2") (pintype "passive"))
      (node (ref "Q4") (pin "2") (pinfunction "S_2") (pintype "passive"))
      (node (ref "Q5") (pin "2") (pinfunction "S_2") (pintype "passive"))
      (node (ref "Q6") (pin "2") (pinfunction "S_2") (pintype "passive"))
      (node (ref "Q7") (pin "2") (pinfunction "S_2") (pintype "passive"))
      (node (ref "Q8") (pin "2") (pinfunction "S_2") (pintype "passive"))
      (node (ref "Q9") (pin "2") (pinfunction "S_2") (pintype "passive"))
      (node (ref "R1") (pin "1") (pintype "passive"))
      (node (ref "R10") (pin "1") (pintype "passive"))
      (node (ref "R11") (pin "1") (pintype "passive"))
      (node (ref "R15") (pin "1") (pintype "passive"))
      (node (ref "R16") (pin "1") (pintype "passive"))
      (node (ref "R19") (pin "1") (pintype "passive"))
      (node (ref "R2") (pin "1") (pintype "passive"))
      (node (ref "R20") (pin "1") (pintype "passive"))
      (node (ref "R23") (pin "1") (pintype "passive"))
      (node (ref "R24") (pin "1") (pintype "passive"))
      (node (ref "R6") (pin "1") (pintype "passive"))
      (node (ref "R7") (pin "1") (pintype "passive"))
    )
    (net (code "93") (name "VCC_2") (class "Default") (node (ref "H1") (pin "4") (pintype "passive")))
    (net (code "94") (name "V_MCU") (class "Default")
      (node (ref "H1") (pin "7") (pintype "passive"))
      (node (ref "R5") (pin "2") (pintype "passive"))
      (node (ref "U2") (pin "1") (pinfunction "VIN_1") (pintype "passive"))
    )
    (net (code "95") (name "unconnected-(J1-A8-Pad6)") (class "Default")
      (node (ref "J1") (pin "6") (pinfunction "A8_6") (pintype "passive+no_connect"))
    )
    (net (code "96") (name "unconnected-(J1-B8-Pad12)") (class "Default")
      (node (ref "J1") (pin "12") (pinfunction "B8_12") (pintype "passive+no_connect"))
    )
    (net (code "97") (name "unconnected-(U2-N{slash}C-Pad4)") (class "Default")
      (node (ref "U2") (pin "4") (pinfunction "N/C_4") (pintype "passive+no_connect"))
    )
    (net (code "98") (name "unconnected-(U4-Q0-Pad15)") (class "Default")
      (node (ref "U4") (pin "15") (pinfunction "Q0_15") (pintype "passive+no_connect"))
    )
    (net (code "99") (name "unconnected-(U5-Q0-Pad15)") (class "Default")
      (node (ref "U5") (pin "15") (pinfunction "Q0_15") (pintype "passive+no_connect"))
    )
    (net (code "100") (name "unconnected-(U5-Q6-Pad6)") (class "Default")
      (node (ref "U5") (pin "6") (pinfunction "Q6_6") (pintype "passive+no_connect"))
    )
    (net (code "101") (name "unconnected-(U5-Q7'-Pad9)") (class "Default")
      (node (ref "U5") (pin "9") (pinfunction "Q7'_9") (pintype "passive+no_connect"))
    )
    (net (code "102") (name "unconnected-(U5-Q7-Pad7)") (class "Default")
      (node (ref "U5") (pin "7") (pinfunction "Q7_7") (pintype "passive+no_connect"))
    )
    (net (code "103") (name "unconnected-(U6-SDO-Pad14)") (class "Default")
      (node (ref "U6") (pin "14") (pinfunction "SDO_14") (pintype "passive+no_connect"))
    )
    (net (code "104") (name "unconnected-(U7-N{slash}C-Pad4)") (class "Default")
      (node (ref "U7") (pin "4") (pinfunction "N/C_4") (pintype "passive+no_connect"))
    )
  )
)
